# host.net
KiCad netlist of a schematic drawn in Altium Designer
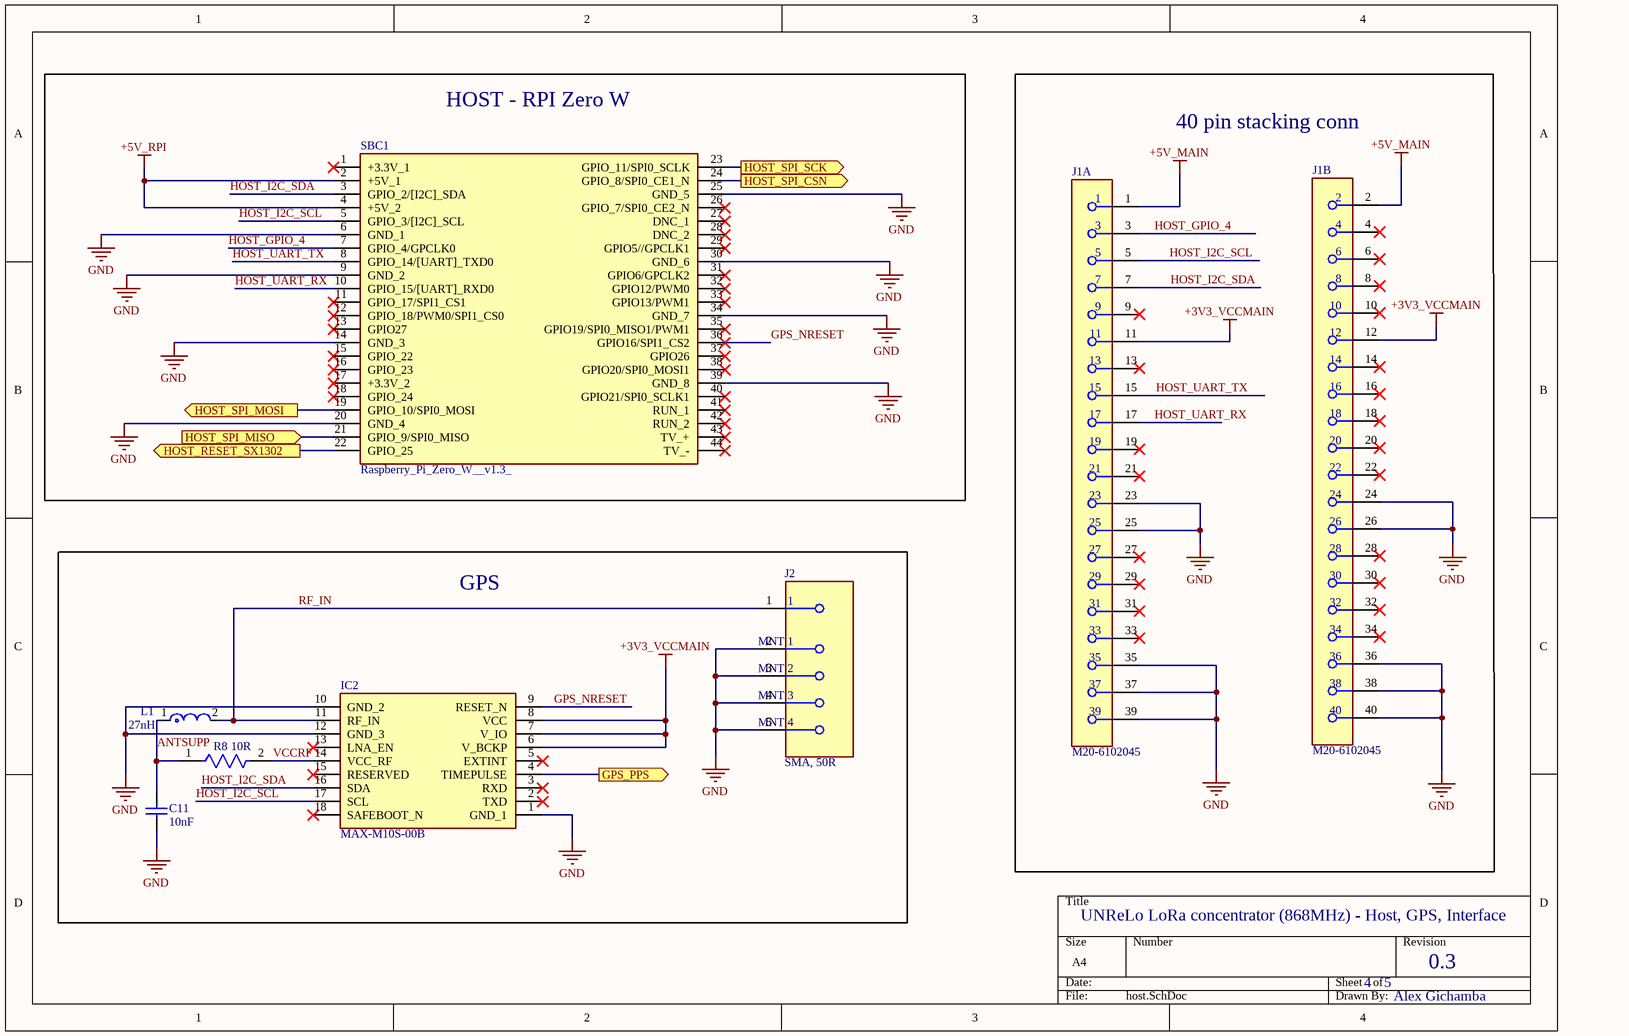
[diagram p0: host.SchDoc]

(export (version "E")
  (design (tool "Eeschema 10.0.6"))
  (components
    (comp (ref "C11")
      (value "10nF")
      (footprint "CAPC1608X90X35NL15T15")
      (fields
        (field (name "MANUFACTURER") "AVX Interconnect / Elco")
        (field (name "PART NUMBER") "0603YC103JAT2A")
      )
      (libsource (lib "Altium Content Vault") (part "CAP"))
    )
    (comp (ref "IC2")
      (value "MAX-M10S-00B")
      (footprint "SamacSys:MAXM10S00B")
      (description "Integrated Circuit")
      (fields (field (name "MOUSER PART NUMBER") "377-MAX-M10S-00B"))
      (libsource (lib "*") (part "MAX-M10S-00B"))
    )
    (comp (ref "J1")
      (value "M20-6102045")
      (footprint "FP-M20-6102045-MFG")
      (description "CONN STKTHRU PC/104 40POS PCB")
      (libsource (lib "Altium Content Vault") (part "7acf1c4a8db21028d11741a46a6ec78"))
    )
    (comp (ref "J2")
      (value "SMA, 50R")
      (footprint "FP-SMA-J-P-H-ST-EM1-MFG")
      (description "CONN SMA JACK STR 50OHM EDGE MNT")
      (libsource (lib "Altium Content Vault") (part "c65b8a639cdaef1819ea20b5466f8fa"))
    )
    (comp (ref "L1")
      (value "27nH")
      (footprint "FP-LQG15HH_02-IPC_C")
      (description "Multilayer type RF Inductor 27nH ±5% 0.46Ω 350mA 0402")
      (fields (field (name "TOLERANCE") "5%"))
      (libsource (lib "Altium Content Vault") (part "4cc4b267dca4c8e51f7102f422741d8"))
    )
    (comp (ref "R8")
      (value "10R")
      (footprint "FP-ERJ3EK-MFG")
      (description "RES SMD 10 OHM 1% 1/10W 0603")
      (fields
        (field (name "OCTOPART") "https://octopart.com/erj-3ekf10r0v-panasonic-55403649")
        (field (name "MANUFACTURER PART NUMBER") "ERJ-3EKF10R0V")
      )
      (libsource (lib "Altium Content Vault") (part "1029c3af85768c4190bb7ad29bc67b5"))
    )
    (comp (ref "SBC1")
      (value "Raspberry_Pi_Zero_W__v1.3_")
      (footprint "SamacSys:RASPBERRYPIZEROWV13")
      (description "Integrated Circuit")
      (fields (field (name "MANUFACTURER_PART_NUMBER") "Raspberry Pi Zero W (v1.3)"))
      (libsource (lib "*") (part "Raspberry_Pi_Zero_W__v1.3_"))
    )
  )
  (nets
    (net (code "1") (name "+3V3_VCCMAIN") (class "Default")
      (node (ref "IC2") (pin "6") (pinfunction "V_BCKP_6") (pintype "passive"))
      (node (ref "IC2") (pin "7") (pinfunction "V_IO_7") (pintype "passive"))
      (node (ref "IC2") (pin "8") (pinfunction "VCC_8") (pintype "passive"))
      (node (ref "J1") (pin "11") (pinfunction "11_11") (pintype "passive"))
      (node (ref "J1") (pin "12") (pinfunction "12_12") (pintype "passive"))
    )
    (net (code "2") (name "+5V_MAIN") (class "Default")
      (node (ref "J1") (pin "1") (pinfunction "1_1") (pintype "passive"))
      (node (ref "J1") (pin "2") (pinfunction "2_2") (pintype "passive"))
    )
    (net (code "3") (name "+5V_RPI") (class "Default")
      (node (ref "SBC1") (pin "2") (pinfunction "+5V_1_2") (pintype "passive"))
      (node (ref "SBC1") (pin "4") (pinfunction "+5V_2_4") (pintype "passive"))
    )
    (net (code "4") (name "/ANTSUPP") (class "Default")
      (node (ref "C11") (pin "2") (pinfunction "2_2") (pintype "passive"))
      (node (ref "L1") (pin "1") (pinfunction "1_1") (pintype "passive"))
      (node (ref "R8") (pin "1") (pinfunction "1_1") (pintype "passive"))
    )
    (net (code "5") (name "/GPS_NRESET") (class "Default")
      (node (ref "IC2") (pin "9") (pinfunction "RESET_N_9") (pintype "passive"))
      (node (ref "SBC1") (pin "36") (pinfunction "GPIO16/SPI1_CS2_36") (pintype "passive"))
    )
    (net (code "6") (name "/GPS_PPS") (class "Default")
      (node (ref "IC2") (pin "4") (pinfunction "TIMEPULSE_4") (pintype "passive"))
    )
    (net (code "7") (name "/HOST_GPIO_4") (class "Default")
      (node (ref "J1") (pin "3") (pinfunction "3_3") (pintype "passive"))
      (node (ref "SBC1") (pin "7") (pinfunction "GPIO_4/GPCLK0_7") (pintype "passive"))
    )
    (net (code "8") (name "/HOST_I2C_SCL") (class "Default")
      (node (ref "IC2") (pin "17") (pinfunction "SCL_17") (pintype "passive"))
      (node (ref "J1") (pin "5") (pinfunction "5_5") (pintype "passive"))
      (node (ref "SBC1") (pin "5") (pinfunction "GPIO_3/[I2C]_SCL_5") (pintype "passive"))
    )
    (net (code "9") (name "/HOST_I2C_SDA") (class "Default")
      (node (ref "IC2") (pin "16") (pinfunction "SDA_16") (pintype "passive"))
      (node (ref "J1") (pin "7") (pinfunction "7_7") (pintype "passive"))
      (node (ref "SBC1") (pin "3") (pinfunction "GPIO_2/[I2C]_SDA_3") (pintype "passive"))
    )
    (net (code "10") (name "/HOST_RESET_SX1302") (class "Default")
      (node (ref "SBC1") (pin "22") (pinfunction "GPIO_25_22") (pintype "passive"))
    )
    (net (code "11") (name "/HOST_SPI_CSN") (class "Default")
      (node (ref "SBC1") (pin "24") (pinfunction "GPIO_8/SPI0_CE1_N_24") (pintype "passive"))
    )
    (net (code "12") (name "/HOST_SPI_MISO") (class "Default")
      (node (ref "SBC1") (pin "21") (pinfunction "GPIO_9/SPI0_MISO_21") (pintype "passive"))
    )
    (net (code "13") (name "/HOST_SPI_MOSI") (class "Default")
      (node (ref "SBC1") (pin "19") (pinfunction "GPIO_10/SPI0_MOSI_19") (pintype "passive"))
    )
    (net (code "14") (name "/HOST_SPI_SCK") (class "Default")
      (node (ref "SBC1") (pin "23") (pinfunction "GPIO_11/SPI0_SCLK_23") (pintype "passive"))
    )
    (net (code "15") (name "/HOST_UART_RX") (class "Default")
      (node (ref "J1") (pin "17") (pinfunction "17_17") (pintype "passive"))
      (node (ref "SBC1") (pin "10") (pinfunction "GPIO_15/[UART]_RXD0_10") (pintype "passive"))
    )
    (net (code "16") (name "/HOST_UART_TX") (class "Default")
      (node (ref "J1") (pin "15") (pinfunction "15_15") (pintype "passive"))
      (node (ref "SBC1") (pin "8") (pinfunction "GPIO_14/[UART]_TXD0_8") (pintype "passive"))
    )
    (net (code "17") (name "/RF_IN") (class "Default")
      (node (ref "IC2") (pin "11") (pinfunction "RF_IN_11") (pintype "passive"))
      (node (ref "J2") (pin "1") (pinfunction "1_1") (pintype "passive"))
      (node (ref "L1") (pin "2") (pinfunction "2_2") (pintype "passive"))
    )
    (net (code "18") (name "/VCCRF") (class "Default")
      (node (ref "IC2") (pin "14") (pinfunction "VCC_RF_14") (pintype "passive"))
      (node (ref "R8") (pin "2") (pinfunction "2_2") (pintype "passive"))
    )
    (net (code "19") (name "GND") (class "Default")
      (node (ref "C11") (pin "1") (pinfunction "1_1") (pintype "passive"))
      (node (ref "IC2") (pin "1") (pinfunction "GND_1_1") (pintype "passive"))
      (node (ref "IC2") (pin "10") (pinfunction "GND_2_10") (pintype "passive"))
      (node (ref "IC2") (pin "12") (pinfunction "GND_3_12") (pintype "passive"))
      (node (ref "J1") (pin "23") (pinfunction "23_23") (pintype "passive"))
      (node (ref "J1") (pin "24") (pinfunction "24_24") (pintype "passive"))
      (node (ref "J1") (pin "25") (pinfunction "25_25") (pintype "passive"))
      (node (ref "J1") (pin "26") (pinfunction "26_26") (pintype "passive"))
      (node (ref "J1") (pin "35") (pinfunction "35_35") (pintype "passive"))
      (node (ref "J1") (pin "36") (pinfunction "36_36") (pintype "passive"))
      (node (ref "J1") (pin "37") (pinfunction "37_37") (pintype "passive"))
      (node (ref "J1") (pin "38") (pinfunction "38_38") (pintype "passive"))
      (node (ref "J1") (pin "39") (pinfunction "39_39") (pintype "passive"))
      (node (ref "J1") (pin "40") (pinfunction "40_40") (pintype "passive"))
      (node (ref "J2") (pin "2") (pinfunction "MNT_1_2") (pintype "passive"))
      (node (ref "J2") (pin "3") (pinfunction "MNT_2_3") (pintype "passive"))
      (node (ref "J2") (pin "4") (pinfunction "MNT_3_4") (pintype "passive"))
      (node (ref "J2") (pin "5") (pinfunction "MNT_4_5") (pintype "passive"))
      (node (ref "SBC1") (pin "14") (pinfunction "GND_3_14") (pintype "passive"))
      (node (ref "SBC1") (pin "20") (pinfunction "GND_4_20") (pintype "passive"))
      (node (ref "SBC1") (pin "25") (pinfunction "GND_5_25") (pintype "passive"))
      (node (ref "SBC1") (pin "30") (pinfunction "GND_6_30") (pintype "passive"))
      (node (ref "SBC1") (pin "34") (pinfunction "GND_7_34") (pintype "passive"))
      (node (ref "SBC1") (pin "39") (pinfunction "GND_8_39") (pintype "passive"))
      (node (ref "SBC1") (pin "6") (pinfunction "GND_1_6") (pintype "passive"))
      (node (ref "SBC1") (pin "9") (pinfunction "GND_2_9") (pintype "passive"))
    )
    (net (code "20") (name "unconnected-(IC2-EXTINT-Pad5)") (class "Default")
      (node (ref "IC2") (pin "5") (pinfunction "EXTINT_5") (pintype "passive+no_connect"))
    )
    (net (code "21") (name "unconnected-(IC2-LNA_EN-Pad13)") (class "Default")
      (node (ref "IC2") (pin "13") (pinfunction "LNA_EN_13") (pintype "passive+no_connect"))
    )
    (net (code "22") (name "unconnected-(IC2-RESERVED-Pad15)") (class "Default")
      (node (ref "IC2") (pin "15") (pinfunction "RESERVED_15") (pintype "passive+no_connect"))
    )
    (net (code "23") (name "unconnected-(IC2-RXD-Pad3)") (class "Default")
      (node (ref "IC2") (pin "3") (pinfunction "RXD_3") (pintype "passive+no_connect"))
    )
    (net (code "24") (name "unconnected-(IC2-SAFEBOOT_N-Pad18)") (class "Default")
      (node (ref "IC2") (pin "18") (pinfunction "SAFEBOOT_N_18") (pintype "passive+no_connect"))
    )
    (net (code "25") (name "unconnected-(IC2-TXD-Pad2)") (class "Default")
      (node (ref "IC2") (pin "2") (pinfunction "TXD_2") (pintype "passive+no_connect"))
    )
    (net (code "26") (name "unconnected-(J1-Pad4)") (class "Default")
      (node (ref "J1") (pin "4") (pinfunction "4_4") (pintype "passive+no_connect"))
    )
    (net (code "27") (name "unconnected-(J1-Pad6)") (class "Default")
      (node (ref "J1") (pin "6") (pinfunction "6_6") (pintype "passive+no_connect"))
    )
    (net (code "28") (name "unconnected-(J1-Pad8)") (class "Default")
      (node (ref "J1") (pin "8") (pinfunction "8_8") (pintype "passive+no_connect"))
    )
    (net (code "29") (name "unconnected-(J1-Pad9)") (class "Default")
      (node (ref "J1") (pin "9") (pinfunction "9_9") (pintype "passive+no_connect"))
    )
    (net (code "30") (name "unconnected-(J1-Pad10)") (class "Default")
      (node (ref "J1") (pin "10") (pinfunction "10_10") (pintype "passive+no_connect"))
    )
    (net (code "31") (name "unconnected-(J1-Pad13)") (class "Default")
      (node (ref "J1") (pin "13") (pinfunction "13_13") (pintype "passive+no_connect"))
    )
    (net (code "32") (name "unconnected-(J1-Pad14)") (class "Default")
      (node (ref "J1") (pin "14") (pinfunction "14_14") (pintype "passive+no_connect"))
    )
    (net (code "33") (name "unconnected-(J1-Pad16)") (class "Default")
      (node (ref "J1") (pin "16") (pinfunction "16_16") (pintype "passive+no_connect"))
    )
    (net (code "34") (name "unconnected-(J1-Pad18)") (class "Default")
      (node (ref "J1") (pin "18") (pinfunction "18_18") (pintype "passive+no_connect"))
    )
    (net (code "35") (name "unconnected-(J1-Pad19)") (class "Default")
      (node (ref "J1") (pin "19") (pinfunction "19_19") (pintype "passive+no_connect"))
    )
    (net (code "36") (name "unconnected-(J1-Pad20)") (class "Default")
      (node (ref "J1") (pin "20") (pinfunction "20_20") (pintype "passive+no_connect"))
    )
    (net (code "37") (name "unconnected-(J1-Pad21)") (class "Default")
      (node (ref "J1") (pin "21") (pinfunction "21_21") (pintype "passive+no_connect"))
    )
    (net (code "38") (name "unconnected-(J1-Pad22)") (class "Default")
      (node (ref "J1") (pin "22") (pinfunction "22_22") (pintype "passive+no_connect"))
    )
    (net (code "39") (name "unconnected-(J1-Pad27)") (class "Default")
      (node (ref "J1") (pin "27") (pinfunction "27_27") (pintype "passive+no_connect"))
    )
    (net (code "40") (name "unconnected-(J1-Pad28)") (class "Default")
      (node (ref "J1") (pin "28") (pinfunction "28_28") (pintype "passive+no_connect"))
    )
    (net (code "41") (name "unconnected-(J1-Pad29)") (class "Default")
      (node (ref "J1") (pin "29") (pinfunction "29_29") (pintype "passive+no_connect"))
    )
    (net (code "42") (name "unconnected-(J1-Pad30)") (class "Default")
      (node (ref "J1") (pin "30") (pinfunction "30_30") (pintype "passive+no_connect"))
    )
    (net (code "43") (name "unconnected-(J1-Pad31)") (class "Default")
      (node (ref "J1") (pin "31") (pinfunction "31_31") (pintype "passive+no_connect"))
    )
    (net (code "44") (name "unconnected-(J1-Pad32)") (class "Default")
      (node (ref "J1") (pin "32") (pinfunction "32_32") (pintype "passive+no_connect"))
    )
    (net (code "45") (name "unconnected-(J1-Pad33)") (class "Default")
      (node (ref "J1") (pin "33") (pinfunction "33_33") (pintype "passive+no_connect"))
    )
    (net (code "46") (name "unconnected-(J1-Pad34)") (class "Default")
      (node (ref "J1") (pin "34") (pinfunction "34_34") (pintype "passive+no_connect"))
    )
    (net (code "47") (name "unconnected-(SBC1-+3.3V_1-Pad1)") (class "Default")
      (node (ref "SBC1") (pin "1") (pinfunction "+3.3V_1_1") (pintype "passive+no_connect"))
    )
    (net (code "48") (name "unconnected-(SBC1-+3.3V_2-Pad17)") (class "Default")
      (node (ref "SBC1") (pin "17") (pinfunction "+3.3V_2_17") (pintype "passive+no_connect"))
    )
    (net (code "49") (name "unconnected-(SBC1-DNC_1-Pad27)") (class "Default")
      (node (ref "SBC1") (pin "27") (pinfunction "DNC_1_27") (pintype "passive+no_connect"))
    )
    (net (code "50") (name "unconnected-(SBC1-DNC_2-Pad28)") (class "Default")
      (node (ref "SBC1") (pin "28") (pinfunction "DNC_2_28") (pintype "passive+no_connect"))
    )
    (net (code "51") (name "unconnected-(SBC1-GPIO5{slash}{slash}GPCLK1-Pad29)") (class "Default")
      (node (ref "SBC1") (pin "29") (pinfunction "GPIO5//GPCLK1_29") (pintype "passive+no_connect"))
    )
    (net (code "52") (name "unconnected-(SBC1-GPIO6{slash}GPCLK2-Pad31)") (class "Default")
      (node (ref "SBC1") (pin "31") (pinfunction "GPIO6/GPCLK2_31") (pintype "passive+no_connect"))
    )
    (net (code "53") (name "unconnected-(SBC1-GPIO12{slash}PWM0-Pad32)") (class "Default")
      (node (ref "SBC1") (pin "32") (pinfunction "GPIO12/PWM0_32") (pintype "passive+no_connect"))
    )
    (net (code "54") (name "unconnected-(SBC1-GPIO13{slash}PWM1-Pad33)") (class "Default")
      (node (ref "SBC1") (pin "33") (pinfunction "GPIO13/PWM1_33") (pintype "passive+no_connect"))
    )
    (net (code "55") (name "unconnected-(SBC1-GPIO19{slash}SPI0_MISO1{slash}PWM1-Pad35)") (class "Default")
      (node (ref "SBC1") (pin "35") (pinfunction "GPIO19/SPI0_MISO1/PWM1_35") (pintype "passive+no_connect"))
    )
    (net (code "56") (name "unconnected-(SBC1-GPIO20{slash}SPI0_MOSI1-Pad38)") (class "Default")
      (node (ref "SBC1") (pin "38") (pinfunction "GPIO20/SPI0_MOSI1_38") (pintype "passive+no_connect"))
    )
    (net (code "57") (name "unconnected-(SBC1-GPIO21{slash}SPI0_SCLK1-Pad40)") (class "Default")
      (node (ref "SBC1") (pin "40") (pinfunction "GPIO21/SPI0_SCLK1_40") (pintype "passive+no_connect"))
    )
    (net (code "58") (name "unconnected-(SBC1-GPIO26-Pad37)") (class "Default")
      (node (ref "SBC1") (pin "37") (pinfunction "GPIO26_37") (pintype "passive+no_connect"))
    )
    (net (code "59") (name "unconnected-(SBC1-GPIO27-Pad13)") (class "Default")
      (node (ref "SBC1") (pin "13") (pinfunction "GPIO27_13") (pintype "passive+no_connect"))
    )
    (net (code "60") (name "unconnected-(SBC1-GPIO_7{slash}SPI0_CE2_N-Pad26)") (class "Default")
      (node (ref "SBC1") (pin "26") (pinfunction "GPIO_7/SPI0_CE2_N_26") (pintype "passive+no_connect"))
    )
    (net (code "61") (name "unconnected-(SBC1-GPIO_17{slash}SPI1_CS1-Pad11)") (class "Default")
      (node (ref "SBC1") (pin "11") (pinfunction "GPIO_17/SPI1_CS1_11") (pintype "passive+no_connect"))
    )
    (net (code "62") (name "unconnected-(SBC1-GPIO_18{slash}PWM0{slash}SPI1_CS0-Pad12)") (class "Default")
      (node (ref "SBC1") (pin "12") (pinfunction "GPIO_18/PWM0/SPI1_CS0_12") (pintype "passive+no_connect"))
    )
    (net (code "63") (name "unconnected-(SBC1-GPIO_22-Pad15)") (class "Default")
      (node (ref "SBC1") (pin "15") (pinfunction "GPIO_22_15") (pintype "passive+no_connect"))
    )
    (net (code "64") (name "unconnected-(SBC1-GPIO_23-Pad16)") (class "Default")
      (node (ref "SBC1") (pin "16") (pinfunction "GPIO_23_16") (pintype "passive+no_connect"))
    )
    (net (code "65") (name "unconnected-(SBC1-GPIO_24-Pad18)") (class "Default")
      (node (ref "SBC1") (pin "18") (pinfunction "GPIO_24_18") (pintype "passive+no_connect"))
    )
    (net (code "66") (name "unconnected-(SBC1-RUN_1-Pad41)") (class "Default")
      (node (ref "SBC1") (pin "41") (pinfunction "RUN_1_41") (pintype "passive+no_connect"))
    )
    (net (code "67") (name "unconnected-(SBC1-RUN_2-Pad42)") (class "Default")
      (node (ref "SBC1") (pin "42") (pinfunction "RUN_2_42") (pintype "passive+no_connect"))
    )
    (net (code "68") (name "unconnected-(SBC1-TV_+-Pad43)") (class "Default")
      (node (ref "SBC1") (pin "43") (pinfunction "TV_+_43") (pintype "passive+no_connect"))
    )
    (net (code "69") (name "unconnected-(SBC1-TV_--Pad44)") (class "Default")
      (node (ref "SBC1") (pin "44") (pinfunction "TV_-_44") (pintype "passive+no_connect"))
    )
  )
)
